# Button_input.net
KiCad netlist of a schematic drawn in Altium Designer
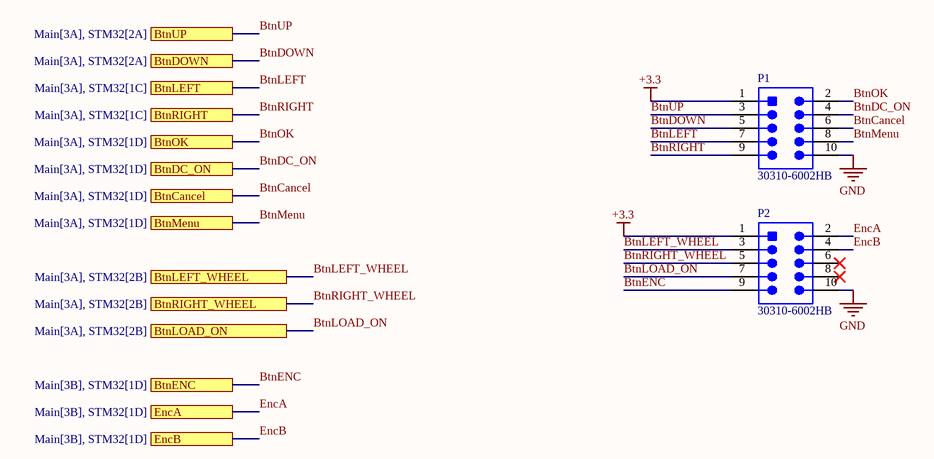
[diagram p0: Button_input.SchDoc]

(export (version "E")
  (design (tool "Eeschema 10.0.6"))
  (components
    (comp (ref "P1")
      (value "30310-6002HB")
      (footprint "3M-30310-6002HB-10_V")
      (fields (field (name "MANUFACTURER") "3M"))
      (libsource (lib "Altium Content Vault") (part "CN-2P-M-R10"))
    )
    (comp (ref "P2")
      (value "30310-6002HB")
      (footprint "3M-30310-6002HB-10_V")
      (fields (field (name "MANUFACTURER") "3M"))
      (libsource (lib "Altium Content Vault") (part "CN-2P-M-R10"))
    )
  )
  (nets
    (net (code "1") (name "+3.3") (class "Default")
      (node (ref "P1") (pin "1") (pinfunction "1_1") (pintype "passive"))
      (node (ref "P2") (pin "1") (pinfunction "1_1") (pintype "passive"))
    )
    (net (code "2") (name "/BtnCancel") (class "Default")
      (node (ref "P1") (pin "6") (pinfunction "6_6") (pintype "passive"))
    )
    (net (code "3") (name "/BtnDC_ON") (class "Default")
      (node (ref "P1") (pin "4") (pinfunction "4_4") (pintype "passive"))
    )
    (net (code "4") (name "/BtnDOWN") (class "Default")
      (node (ref "P1") (pin "5") (pinfunction "5_5") (pintype "passive"))
    )
    (net (code "5") (name "/BtnENC") (class "Default")
      (node (ref "P2") (pin "9") (pinfunction "9_9") (pintype "passive"))
    )
    (net (code "6") (name "/BtnLEFT") (class "Default")
      (node (ref "P1") (pin "7") (pinfunction "7_7") (pintype "passive"))
    )
    (net (code "7") (name "/BtnLEFT_WHEEL") (class "Default")
      (node (ref "P2") (pin "3") (pinfunction "3_3") (pintype "passive"))
    )
    (net (code "8") (name "/BtnLOAD_ON") (class "Default")
      (node (ref "P2") (pin "7") (pinfunction "7_7") (pintype "passive"))
    )
    (net (code "9") (name "/BtnMenu") (class "Default")
      (node (ref "P1") (pin "8") (pinfunction "8_8") (pintype "passive"))
    )
    (net (code "10") (name "/BtnOK") (class "Default")
      (node (ref "P1") (pin "2") (pinfunction "2_2") (pintype "passive"))
    )
    (net (code "11") (name "/BtnRIGHT") (class "Default")
      (node (ref "P1") (pin "9") (pinfunction "9_9") (pintype "passive"))
    )
    (net (code "12") (name "/BtnRIGHT_WHEEL") (class "Default")
      (node (ref "P2") (pin "5") (pinfunction "5_5") (pintype "passive"))
    )
    (net (code "13") (name "/BtnUP") (class "Default")
      (node (ref "P1") (pin "3") (pinfunction "3_3") (pintype "passive"))
    )
    (net (code "14") (name "/EncA") (class "Default")
      (node (ref "P2") (pin "2") (pinfunction "2_2") (pintype "passive"))
    )
    (net (code "15") (name "/EncB") (class "Default")
      (node (ref "P2") (pin "4") (pinfunction "4_4") (pintype "passive"))
    )
    (net (code "16") (name "GND") (class "Default")
      (node (ref "P1") (pin "10") (pinfunction "10_10") (pintype "passive"))
      (node (ref "P2") (pin "10") (pinfunction "10_10") (pintype "passive"))
    )
    (net (code "17") (name "unconnected-(P2-Pad6)") (class "Default")
      (node (ref "P2") (pin "6") (pinfunction "6_6") (pintype "passive+no_connect"))
    )
    (net (code "18") (name "unconnected-(P2-Pad8)") (class "Default")
      (node (ref "P2") (pin "8") (pinfunction "8_8") (pintype "passive+no_connect"))
    )
  )
)
